# SAMV71_Xplained_Ultra_Audio.net
KiCad netlist of a schematic drawn in Altium Designer
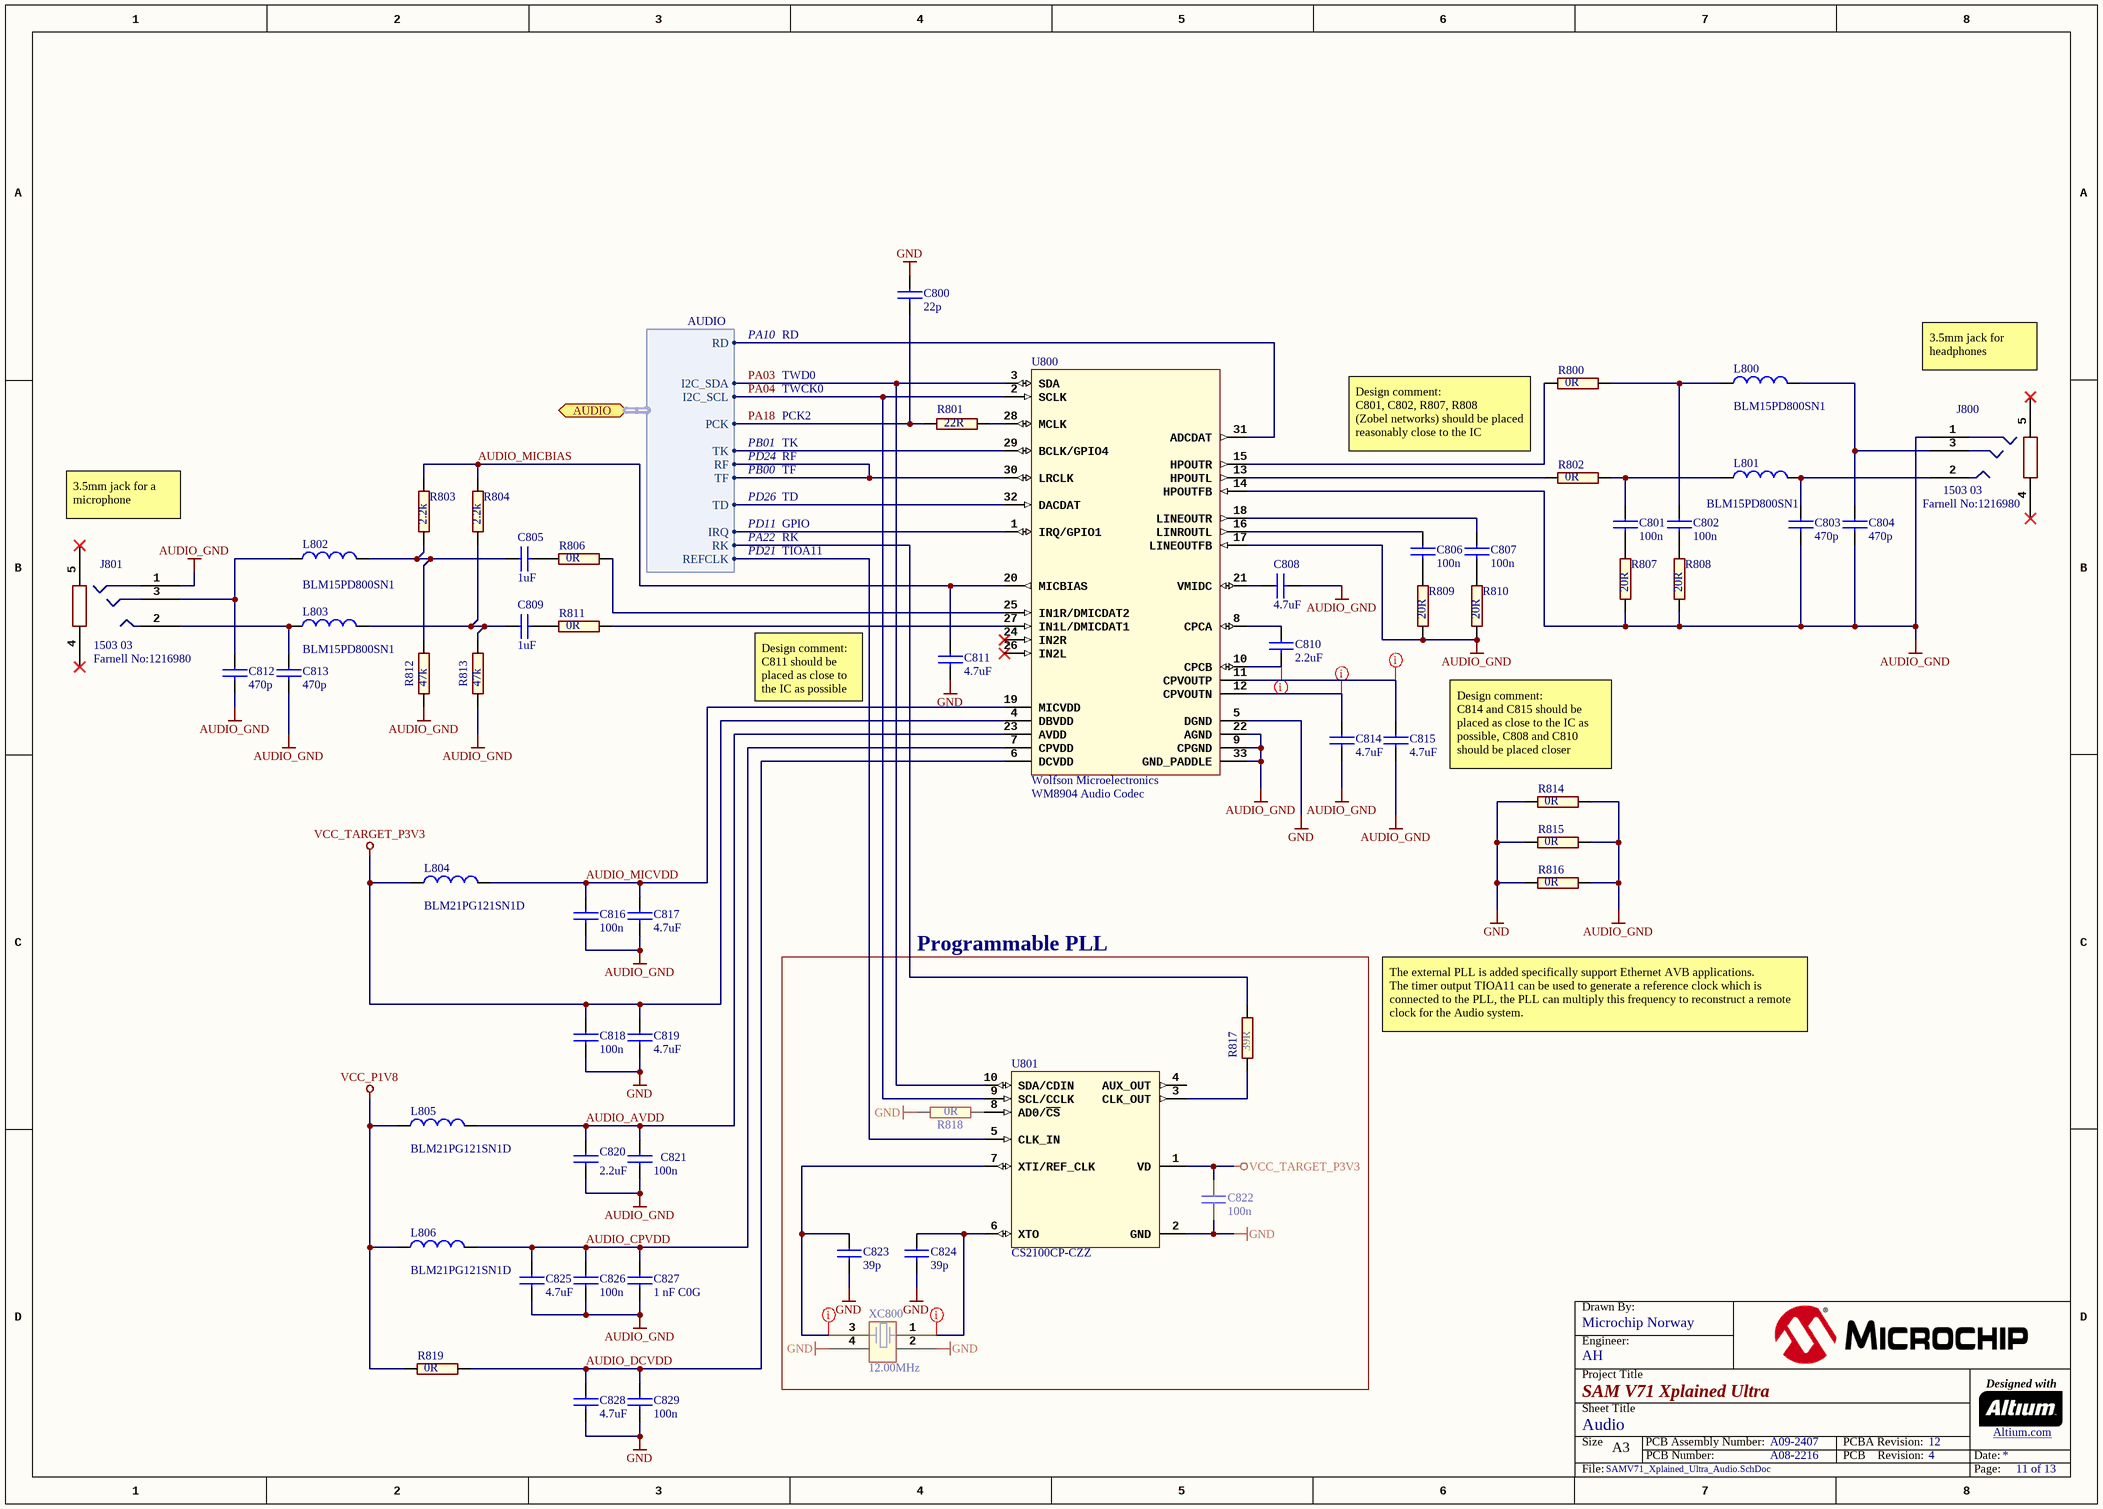
[diagram p0: SAMV71_Xplained_Ultra_Audio.SchDoc]

(export (version "E")
  (design (tool "Eeschema 10.0.6"))
  (components
    (comp (ref "C800")
      (value "22p")
      (footprint "AP1-00001")
      (description "Ceramic capacitor, SMD 0402, NP0, 50V, +/-5%")
      (fields (field (name "TOLERANCE") "50V, +/-5%") (field (name "MANUFACTURER") "YAGEO CORP"))
      (libsource (lib "AltiumDbLib") (part "CAP-NONPOL"))
    )
    (comp (ref "C801")
      (value "100n")
      (footprint "AP1-00001")
      (description "Ceramic capacitor, SMD 0402, X7R, 16V, +/-10%")
      (fields (field (name "TOLERANCE") "16V, +/-10%") (field (name "MANUFACTURER") "Kemet"))
      (libsource (lib "AltiumDbLib") (part "CAP-NONPOL"))
    )
    (comp (ref "C802")
      (value "100n")
      (footprint "AP1-00001")
      (description "Ceramic capacitor, SMD 0402, X7R, 16V, +/-10%")
      (fields (field (name "TOLERANCE") "16V, +/-10%") (field (name "MANUFACTURER") "Kemet"))
      (libsource (lib "AltiumDbLib") (part "CAP-NONPOL"))
    )
    (comp (ref "C803")
      (value "470p")
      (footprint "AP1-00001")
      (description "Ceramic capacitor, SMD 0402, X7R, 50V, +/-10%")
      (fields (field (name "TOLERANCE") "50V, +/-10%") (field (name "MANUFACTURER") "Murata"))
      (libsource (lib "AltiumDbLib") (part "CAP-NONPOL"))
    )
    (comp (ref "C804")
      (value "470p")
      (footprint "AP1-00001")
      (description "Ceramic capacitor, SMD 0402, X7R, 50V, +/-10%")
      (fields (field (name "TOLERANCE") "50V, +/-10%") (field (name "MANUFACTURER") "Murata"))
      (libsource (lib "AltiumDbLib") (part "CAP-NONPOL"))
    )
    (comp (ref "C805")
      (value "1uF")
      (footprint "AP1-00038")
      (description "Ceramic capacitor, SMD 0402, X5R, 10V, ±10 %")
      (fields (field (name "MANUFACTURER") "AVX") (field (name "MPN") "0402ZD105KAT2A"))
      (libsource (lib "AltiumDbLib") (part "CAP-NONPOL"))
    )
    (comp (ref "C806")
      (value "100n")
      (footprint "AP1-00001")
      (description "Ceramic capacitor, SMD 0402, X7R, 16V, +/-10%")
      (fields (field (name "TOLERANCE") "16V, +/-10%") (field (name "MANUFACTURER") "Kemet"))
      (libsource (lib "AltiumDbLib") (part "CAP-NONPOL"))
    )
    (comp (ref "C807")
      (value "100n")
      (footprint "AP1-00001")
      (description "Ceramic capacitor, SMD 0402, X7R, 16V, +/-10%")
      (fields (field (name "TOLERANCE") "16V, +/-10%") (field (name "MANUFACTURER") "Kemet"))
      (libsource (lib "AltiumDbLib") (part "CAP-NONPOL"))
    )
    (comp (ref "C808")
      (value "4.7uF")
      (footprint "AP1-00039")
      (description "Ceramic capacitor, SMD 0603, X5R, 10V, 10% (de31036)")
      (fields (field (name "TOLERANCE") "10%") (field (name "MANUFACTURER") "WALSIN Technology Corporation"))
      (libsource (lib "AltiumDbLib") (part "CAP-NONPOL"))
    )
    (comp (ref "C809")
      (value "1uF")
      (footprint "AP1-00038")
      (description "Ceramic capacitor, SMD 0402, X5R, 10V, ±10 %")
      (fields (field (name "MANUFACTURER") "AVX") (field (name "MPN") "0402ZD105KAT2A"))
      (libsource (lib "AltiumDbLib") (part "CAP-NONPOL"))
    )
    (comp (ref "C810")
      (value "2.2uF")
      (footprint "AP1-00001")
      (description "Ceramic capacitor, SMD 0402, X5R, 6.3V, +/-20%")
      (fields (field (name "TOLERANCE") "Â±20%") (field (name "MANUFACTURER") "Kemet"))
      (libsource (lib "AltiumDbLib") (part "CAP-NONPOL"))
    )
    (comp (ref "C811")
      (value "4.7uF")
      (footprint "AP1-00039")
      (description "Ceramic capacitor, SMD 0603, X5R, 10V, 10% (de31036)")
      (fields (field (name "TOLERANCE") "10%") (field (name "MANUFACTURER") "WALSIN Technology Corporation"))
      (libsource (lib "AltiumDbLib") (part "CAP-NONPOL"))
    )
    (comp (ref "C812")
      (value "470p")
      (footprint "AP1-00001")
      (description "Ceramic capacitor, SMD 0402, X7R, 50V, +/-10%")
      (fields (field (name "TOLERANCE") "50V, +/-10%") (field (name "MANUFACTURER") "Murata"))
      (libsource (lib "AltiumDbLib") (part "CAP-NONPOL"))
    )
    (comp (ref "C813")
      (value "470p")
      (footprint "AP1-00001")
      (description "Ceramic capacitor, SMD 0402, X7R, 50V, +/-10%")
      (fields (field (name "TOLERANCE") "50V, +/-10%") (field (name "MANUFACTURER") "Murata"))
      (libsource (lib "AltiumDbLib") (part "CAP-NONPOL"))
    )
    (comp (ref "C814")
      (value "4.7uF")
      (footprint "AP1-00001")
      (description "Ceramic capacitor, SMD 0402, X5R, 6.3V, +/-20% (de33687)")
      (fields (field (name "TOLERANCE") "+-20%") (field (name "MANUFACTURER") "Murata"))
      (libsource (lib "AltiumDbLib") (part "CAP-NONPOL"))
    )
    (comp (ref "C815")
      (value "4.7uF")
      (footprint "AP1-00001")
      (description "Ceramic capacitor, SMD 0402, X5R, 6.3V, +/-20% (de33687)")
      (fields (field (name "TOLERANCE") "+-20%") (field (name "MANUFACTURER") "Murata"))
      (libsource (lib "AltiumDbLib") (part "CAP-NONPOL"))
    )
    (comp (ref "C816")
      (value "100n")
      (footprint "AP1-00001")
      (description "Ceramic capacitor, SMD 0402, X7R, 16V, +/-10%")
      (fields (field (name "TOLERANCE") "16V, +/-10%") (field (name "MANUFACTURER") "Kemet"))
      (libsource (lib "AltiumDbLib") (part "CAP-NONPOL"))
    )
    (comp (ref "C817")
      (value "4.7uF")
      (footprint "AP1-00039")
      (description "Ceramic capacitor, SMD 0603, X5R, 10V, 10% (de31036)")
      (fields (field (name "TOLERANCE") "10%") (field (name "MANUFACTURER") "WALSIN Technology Corporation"))
      (libsource (lib "AltiumDbLib") (part "CAP-NONPOL"))
    )
    (comp (ref "C818")
      (value "100n")
      (footprint "AP1-00001")
      (description "Ceramic capacitor, SMD 0402, X7R, 16V, +/-10%")
      (fields (field (name "TOLERANCE") "16V, +/-10%") (field (name "MANUFACTURER") "Kemet"))
      (libsource (lib "AltiumDbLib") (part "CAP-NONPOL"))
    )
    (comp (ref "C819")
      (value "4.7uF")
      (footprint "AP1-00039")
      (description "Ceramic capacitor, SMD 0603, X5R, 10V, 10% (de31036)")
      (fields (field (name "TOLERANCE") "10%") (field (name "MANUFACTURER") "WALSIN Technology Corporation"))
      (libsource (lib "AltiumDbLib") (part "CAP-NONPOL"))
    )
    (comp (ref "C820")
      (value "2.2uF")
      (footprint "AP1-00001")
      (description "Ceramic capacitor, SMD 0402, X5R, 6.3V, +/-20%")
      (fields (field (name "TOLERANCE") "Â±20%") (field (name "MANUFACTURER") "Kemet"))
      (libsource (lib "AltiumDbLib") (part "CAP-NONPOL"))
    )
    (comp (ref "C821")
      (value "100n")
      (footprint "AP1-00001")
      (description "Ceramic capacitor, SMD 0402, X7R, 16V, +/-10%")
      (fields (field (name "TOLERANCE") "16V, +/-10%") (field (name "MANUFACTURER") "Kemet"))
      (libsource (lib "AltiumDbLib") (part "CAP-NONPOL"))
    )
    (comp (ref "C822")
      (value "100n")
      (footprint "AP1-00001")
      (description "Ceramic capacitor, SMD 0402, X7R, 16V, +/-10%")
      (fields (field (name "TOLERANCE") "16V, +/-10%") (field (name "MANUFACTURER") "Kemet"))
      (libsource (lib "AltiumDbLib") (part "CAP-NONPOL"))
    )
    (comp (ref "C823")
      (value "39p")
      (footprint "AP1-00001")
      (description "Ceramic capacitor, SMD 0402, NP0, 50V, +/-5%")
      (fields (field (name "TOLERANCE") "50V, +/-5%"))
      (libsource (lib "AltiumDbLib") (part "CAP-NONPOL"))
    )
    (comp (ref "C824")
      (value "39p")
      (footprint "AP1-00001")
      (description "Ceramic capacitor, SMD 0402, NP0, 50V, +/-5%")
      (fields (field (name "TOLERANCE") "50V, +/-5%"))
      (libsource (lib "AltiumDbLib") (part "CAP-NONPOL"))
    )
    (comp (ref "C825")
      (value "4.7uF")
      (footprint "AP1-00039")
      (description "Ceramic capacitor, SMD 0603, X5R, 10V, 10% (de31036)")
      (fields (field (name "TOLERANCE") "10%") (field (name "MANUFACTURER") "WALSIN Technology Corporation"))
      (libsource (lib "AltiumDbLib") (part "CAP-NONPOL"))
    )
    (comp (ref "C826")
      (value "100n")
      (footprint "AP1-00001")
      (description "Ceramic capacitor, SMD 0402, X7R, 16V, +/-10%")
      (fields (field (name "TOLERANCE") "16V, +/-10%") (field (name "MANUFACTURER") "Kemet"))
      (libsource (lib "AltiumDbLib") (part "CAP-NONPOL"))
    )
    (comp (ref "C827")
      (value "1 nF C0G")
      (footprint "AP1-00001")
      (description "Ceramic capacitor, SMD 0402, C0G, 50V, +/-5%")
      (fields (field (name "TOLERANCE") "5%") (field (name "MANUFACTURER") "Murata"))
      (libsource (lib "AltiumDbLib") (part "CAP-NONPOL"))
    )
    (comp (ref "C828")
      (value "4.7uF")
      (footprint "AP1-00039")
      (description "Ceramic capacitor, SMD 0603, X5R, 10V, 10% (de31036)")
      (fields (field (name "TOLERANCE") "10%") (field (name "MANUFACTURER") "WALSIN Technology Corporation"))
      (libsource (lib "AltiumDbLib") (part "CAP-NONPOL"))
    )
    (comp (ref "C829")
      (value "100n")
      (footprint "AP1-00001")
      (description "Ceramic capacitor, SMD 0402, X7R, 16V, +/-10%")
      (fields (field (name "TOLERANCE") "16V, +/-10%") (field (name "MANUFACTURER") "Kemet"))
      (libsource (lib "AltiumDbLib") (part "CAP-NONPOL"))
    )
    (comp (ref "J800")
      (value "Farnell No:1216980")
      (footprint "AP8-00397")
      (description "3.5mm stereo phone jack")
      (fields
        (field (name "ALTIUM_VALUE") "1503 03")
        (field (name "MANUFACTURER") "Lumberg")
        (field (name "MPN") "1503 03")
      )
      (libsource (lib "AltiumDbLib") (part "Jack_Stereo_1503_03"))
    )
    (comp (ref "J801")
      (value "Farnell No:1216980")
      (footprint "AP8-00397")
      (description "3.5mm stereo phone jack")
      (fields
        (field (name "ALTIUM_VALUE") "1503 03")
        (field (name "MANUFACTURER") "Lumberg")
        (field (name "MPN") "1503 03")
      )
      (libsource (lib "") (part "Jack_Stereo_1503_03_1"))
    )
    (comp (ref "L800")
      (value "BLM15PD800SN1")
      (footprint "AP3-00028")
      (description "FERRITE CHIP 80 OHM 1500MA 0402")
      (fields (field (name "TOLERANCE") "±25%") (field (name "MANUFACTURER") "Murata"))
      (libsource (lib "AltiumDbLib") (part "INDUCTOR"))
    )
    (comp (ref "L801")
      (value "BLM15PD800SN1")
      (footprint "AP3-00028")
      (description "FERRITE CHIP 80 OHM 1500MA 0402")
      (fields (field (name "TOLERANCE") "±25%") (field (name "MANUFACTURER") "Murata"))
      (libsource (lib "AltiumDbLib") (part "INDUCTOR"))
    )
    (comp (ref "L802")
      (value "BLM15PD800SN1")
      (footprint "AP3-00028")
      (description "FERRITE CHIP 80 OHM 1500MA 0402")
      (fields (field (name "TOLERANCE") "±25%") (field (name "MANUFACTURER") "Murata"))
      (libsource (lib "AltiumDbLib") (part "INDUCTOR"))
    )
    (comp (ref "L803")
      (value "BLM15PD800SN1")
      (footprint "AP3-00028")
      (description "FERRITE CHIP 80 OHM 1500MA 0402")
      (fields (field (name "TOLERANCE") "±25%") (field (name "MANUFACTURER") "Murata"))
      (libsource (lib "AltiumDbLib") (part "INDUCTOR"))
    )
    (comp (ref "L804")
      (value "BLM21PG121SN1D")
      (footprint "AP3-00104")
      (fields (field (name "MANUFACTURER") "Murata"))
      (libsource (lib "AltiumDbLib") (part "INDUCTOR"))
    )
    (comp (ref "L805")
      (value "BLM21PG121SN1D")
      (footprint "AP3-00104")
      (fields (field (name "MANUFACTURER") "Murata"))
      (libsource (lib "AltiumDbLib") (part "INDUCTOR"))
    )
    (comp (ref "L806")
      (value "BLM21PG121SN1D")
      (footprint "AP3-00104")
      (fields (field (name "MANUFACTURER") "Murata"))
      (libsource (lib "AltiumDbLib") (part "INDUCTOR"))
    )
    (comp (ref "R800")
      (value "0R")
      (footprint "AP2-00000")
      (description "RES 0.0 OHM 1/16W 0402 SMD")
      (fields (field (name "TOLERANCE") "1 %") (field (name "MANUFACTURER") "(n/a)"))
      (libsource (lib "AltiumDbLib") (part "R2"))
    )
    (comp (ref "R801")
      (value "22R")
      (footprint "AP2-00000")
      (description "Thick film resistor, SMD 0402, 1/16W, 1% (de23607)")
      (fields (field (name "TOLERANCE") "1 %") (field (name "MANUFACTURER") "Samsung"))
      (libsource (lib "AltiumDbLib") (part "R2"))
    )
    (comp (ref "R802")
      (value "0R")
      (footprint "AP2-00000")
      (description "RES 0.0 OHM 1/16W 0402 SMD")
      (fields (field (name "TOLERANCE") "1 %") (field (name "MANUFACTURER") "(n/a)"))
      (libsource (lib "AltiumDbLib") (part "R2"))
    )
    (comp (ref "R803")
      (value "2.2k")
      (footprint "AP2-00000")
      (description "Thick film resistor, SMD 0402, 1/16W, 1%")
      (fields (field (name "TOLERANCE") "1 %") (field (name "MANUFACTURER") "ASJ"))
      (libsource (lib "") (part "R2_1"))
    )
    (comp (ref "R804")
      (value "2.2k")
      (footprint "AP2-00000")
      (description "Thick film resistor, SMD 0402, 1/16W, 1%")
      (fields (field (name "TOLERANCE") "1 %") (field (name "MANUFACTURER") "ASJ"))
      (libsource (lib "") (part "R2_1"))
    )
    (comp (ref "R806")
      (value "0R")
      (footprint "AP2-00000")
      (description "RES 0.0 OHM 1/16W 0402 SMD")
      (fields (field (name "TOLERANCE") "1 %") (field (name "MANUFACTURER") "(n/a)"))
      (libsource (lib "AltiumDbLib") (part "R2"))
    )
    (comp (ref "R807")
      (value "20R")
      (footprint "AP2-00000")
      (description "Thick film resistor, SMD 0402, 1/16W, 1%")
      (fields (field (name "TOLERANCE") "1 %") (field (name "MANUFACTURER") "vishay"))
      (libsource (lib "") (part "R2_1"))
    )
    (comp (ref "R808")
      (value "20R")
      (footprint "AP2-00000")
      (description "Thick film resistor, SMD 0402, 1/16W, 1%")
      (fields (field (name "TOLERANCE") "1 %") (field (name "MANUFACTURER") "vishay"))
      (libsource (lib "") (part "R2_1"))
    )
    (comp (ref "R809")
      (value "20R")
      (footprint "AP2-00000")
      (description "Thick film resistor, SMD 0402, 1/16W, 1%")
      (fields (field (name "TOLERANCE") "1 %") (field (name "MANUFACTURER") "vishay"))
      (libsource (lib "") (part "R2_1"))
    )
    (comp (ref "R810")
      (value "20R")
      (footprint "AP2-00000")
      (description "Thick film resistor, SMD 0402, 1/16W, 1%")
      (fields (field (name "TOLERANCE") "1 %") (field (name "MANUFACTURER") "vishay"))
      (libsource (lib "") (part "R2_1"))
    )
    (comp (ref "R811")
      (value "0R")
      (footprint "AP2-00000")
      (description "RES 0.0 OHM 1/16W 0402 SMD")
      (fields (field (name "TOLERANCE") "1 %") (field (name "MANUFACTURER") "(n/a)"))
      (libsource (lib "AltiumDbLib") (part "R2"))
    )
    (comp (ref "R812")
      (value "47k")
      (footprint "AP2-00000")
      (description "Thick film resistor, SMD 0402, 1/16W, 1%")
      (fields (field (name "TOLERANCE") "1 %") (field (name "MANUFACTURER") "KOA"))
      (libsource (lib "") (part "R2_1"))
    )
    (comp (ref "R813")
      (value "47k")
      (footprint "AP2-00000")
      (description "Thick film resistor, SMD 0402, 1/16W, 1%")
      (fields (field (name "TOLERANCE") "1 %") (field (name "MANUFACTURER") "KOA"))
      (libsource (lib "") (part "R2_1"))
    )
    (comp (ref "R814")
      (value "0R")
      (footprint "AP2-00000")
      (description "RES 0.0 OHM 1/16W 0402 SMD")
      (fields (field (name "TOLERANCE") "1 %") (field (name "MANUFACTURER") "(n/a)"))
      (libsource (lib "AltiumDbLib") (part "R2"))
    )
    (comp (ref "R815")
      (value "0R")
      (footprint "AP2-00000")
      (description "RES 0.0 OHM 1/16W 0402 SMD")
      (fields (field (name "TOLERANCE") "1 %") (field (name "MANUFACTURER") "(n/a)"))
      (libsource (lib "AltiumDbLib") (part "R2"))
    )
    (comp (ref "R816")
      (value "0R")
      (footprint "AP2-00000")
      (description "RES 0.0 OHM 1/16W 0402 SMD")
      (fields (field (name "TOLERANCE") "1 %") (field (name "MANUFACTURER") "(n/a)"))
      (libsource (lib "AltiumDbLib") (part "R2"))
    )
    (comp (ref "R817")
      (value "39R")
      (footprint "AP2-00000")
      (description "Thick film resistor, SMD 0402, 1/16W, 1%")
      (fields (field (name "TOLERANCE") "1 %") (field (name "MANUFACTURER") "ASJ"))
      (libsource (lib "") (part "R2_1"))
    )
    (comp (ref "R818")
      (value "0R")
      (footprint "AP2-00000")
      (description "RES 0.0 OHM 1/16W 0402 SMD")
      (fields (field (name "TOLERANCE") "1 %") (field (name "MANUFACTURER") "(n/a)"))
      (libsource (lib "AltiumDbLib") (part "R2"))
    )
    (comp (ref "R819")
      (value "0R")
      (footprint "AP2-00000")
      (description "RES 0.0 OHM 1/16W 0402 SMD")
      (fields (field (name "TOLERANCE") "1 %") (field (name "MANUFACTURER") "(n/a)"))
      (libsource (lib "AltiumDbLib") (part "R2"))
    )
    (comp (ref "U800")
      (value "Wolfson Microelectronics")
      (footprint "AP6-00420")
      (description "Ultra Low Power Codec for Portable Audio Applications")
      (fields
        (field (name "ALTIUM_VALUE") "WM8904 Audio Codec")
        (field (name "MANUFACTURER") "Wolfson microelectronics")
        (field (name "MPN") "WM8904CGEFL/RV")
      )
      (libsource (lib "AltiumDbLib") (part "WM8904"))
    )
    (comp (ref "U801")
      (value "CS2100CP-CZZ")
      (footprint "AP6-00097")
      (description "Programmable Phase-Locked Loop Clock Generator")
      (fields (field (name "MANUFACTURER") "CIRRUS LOGIC") (field (name "MPN") "CS2100CP-CZZR"))
      (libsource (lib "AltiumDbLib") (part "CS2100"))
    )
    (comp (ref "XC800")
      (value "12.00MHz")
      (footprint "AP7-00039")
      (description "Fox FQ5032B 12.0MHz SMD crystal 738B-12")
      (fields (field (name "TOLERANCE") "Â±30ppm") (field (name "MANUFACTURER") "Fox  Electronics"))
      (libsource (lib "AltiumDbLib") (part "CRYSTAL1324"))
    )
  )
  (nets
    (net (code "2") (name "/AUDIO_AVDD") (class "Default")
      (node (ref "C820") (pin "1") (pinfunction "1_1") (pintype "passive"))
      (node (ref "C821") (pin "1") (pinfunction "1_1") (pintype "passive"))
      (node (ref "L805") (pin "2") (pinfunction "2_2") (pintype "passive"))
      (node (ref "U800") (pin "23") (pinfunction "AVDD_23") (pintype "power_in"))
    )
    (net (code "3") (name "/AUDIO_CPVDD") (class "Default")
      (node (ref "C825") (pin "1") (pinfunction "1_1") (pintype "passive"))
      (node (ref "C826") (pin "1") (pinfunction "1_1") (pintype "passive"))
      (node (ref "C827") (pin "1") (pinfunction "1_1") (pintype "passive"))
      (node (ref "L806") (pin "2") (pinfunction "2_2") (pintype "passive"))
      (node (ref "U800") (pin "7") (pinfunction "CPVDD_7") (pintype "power_in"))
    )
    (net (code "4") (name "/AUDIO_DCVDD") (class "Default")
      (node (ref "C828") (pin "1") (pinfunction "1_1") (pintype "passive"))
      (node (ref "C829") (pin "1") (pinfunction "1_1") (pintype "passive"))
      (node (ref "R819") (pin "2") (pinfunction "2_2") (pintype "passive"))
      (node (ref "U800") (pin "6") (pinfunction "DCVDD_6") (pintype "power_in"))
    )
    (net (code "5") (name "/AUDIO_MICBIAS") (class "Default")
      (node (ref "C811") (pin "1") (pinfunction "1_1") (pintype "passive"))
      (node (ref "R803") (pin "2") (pinfunction "2_2") (pintype "passive"))
      (node (ref "R804") (pin "2") (pinfunction "2_2") (pintype "passive"))
      (node (ref "U800") (pin "20") (pinfunction "MICBIAS_20") (pintype "output"))
    )
    (net (code "6") (name "/AUDIO_MICVDD") (class "Default")
      (node (ref "C816") (pin "1") (pinfunction "1_1") (pintype "passive"))
      (node (ref "C817") (pin "1") (pinfunction "1_1") (pintype "passive"))
      (node (ref "L804") (pin "2") (pinfunction "2_2") (pintype "passive"))
      (node (ref "U800") (pin "19") (pinfunction "MICVDD_19") (pintype "power_in"))
    )
    (net (code "7") (name "/IRQ") (class "Default")
      (node (ref "U800") (pin "1") (pinfunction "IRQ/GPIO1_1") (pintype "bidirectional"))
    )
    (net (code "8") (name "/PA03") (class "Default")
      (node (ref "U800") (pin "3") (pinfunction "SDA_3") (pintype "bidirectional"))
      (node (ref "U801") (pin "10") (pinfunction "SDA/CDIN_10") (pintype "bidirectional"))
    )
    (net (code "9") (name "/PA04") (class "Default")
      (node (ref "U800") (pin "2") (pinfunction "SCLK_2") (pintype "input"))
      (node (ref "U801") (pin "9") (pinfunction "SCL/CCLK_9") (pintype "input"))
    )
    (net (code "10") (name "/PA18") (class "Default")
      (node (ref "C800") (pin "2") (pinfunction "2_2") (pintype "passive"))
      (node (ref "R801") (pin "1") (pinfunction "1_1") (pintype "passive"))
    )
    (net (code "11") (name "/RD") (class "Default")
      (node (ref "U800") (pin "31") (pinfunction "ADCDAT_31") (pintype "output"))
    )
    (net (code "12") (name "/REFCLK") (class "Default")
      (node (ref "U801") (pin "5") (pinfunction "CLK_IN_5") (pintype "input"))
    )
    (net (code "13") (name "/RF") (class "Default")
      (node (ref "U800") (pin "30") (pinfunction "LRCLK_30") (pintype "bidirectional"))
    )
    (net (code "14") (name "/RK") (class "Default")
      (node (ref "R817") (pin "2") (pinfunction "2_2") (pintype "passive"))
    )
    (net (code "15") (name "/TD") (class "Default")
      (node (ref "U800") (pin "32") (pinfunction "DACDAT_32") (pintype "input"))
    )
    (net (code "16") (name "/TK") (class "Default")
      (node (ref "U800") (pin "29") (pinfunction "BCLK/GPIO4_29") (pintype "bidirectional"))
    )
    (net (code "18") (name "AUDIO_GND") (class "Default")
      (node (ref "C803") (pin "2") (pinfunction "2_2") (pintype "passive"))
      (node (ref "C804") (pin "2") (pinfunction "2_2") (pintype "passive"))
      (node (ref "C808") (pin "2") (pinfunction "2_2") (pintype "passive"))
      (node (ref "C812") (pin "2") (pinfunction "2_2") (pintype "passive"))
      (node (ref "C813") (pin "2") (pinfunction "2_2") (pintype "passive"))
      (node (ref "C814") (pin "2") (pinfunction "2_2") (pintype "passive"))
      (node (ref "C815") (pin "2") (pinfunction "2_2") (pintype "passive"))
      (node (ref "C816") (pin "2") (pinfunction "2_2") (pintype "passive"))
      (node (ref "C817") (pin "2") (pinfunction "2_2") (pintype "passive"))
      (node (ref "C820") (pin "2") (pinfunction "2_2") (pintype "passive"))
      (node (ref "C821") (pin "2") (pinfunction "2_2") (pintype "passive"))
      (node (ref "C825") (pin "2") (pinfunction "2_2") (pintype "passive"))
      (node (ref "C826") (pin "2") (pinfunction "2_2") (pintype "passive"))
      (node (ref "C827") (pin "2") (pinfunction "2_2") (pintype "passive"))
      (node (ref "J800") (pin "1") (pinfunction "GND_1") (pintype "passive"))
      (node (ref "J801") (pin "1") (pinfunction "GND_1") (pintype "passive"))
      (node (ref "R807") (pin "1") (pinfunction "1_1") (pintype "passive"))
      (node (ref "R808") (pin "1") (pinfunction "1_1") (pintype "passive"))
      (node (ref "R809") (pin "1") (pinfunction "1_1") (pintype "passive"))
      (node (ref "R810") (pin "1") (pinfunction "1_1") (pintype "passive"))
      (node (ref "R812") (pin "1") (pinfunction "1_1") (pintype "passive"))
      (node (ref "R813") (pin "1") (pinfunction "1_1") (pintype "passive"))
      (node (ref "R814") (pin "2") (pinfunction "2_2") (pintype "passive"))
      (node (ref "R815") (pin "2") (pinfunction "2_2") (pintype "passive"))
      (node (ref "R816") (pin "2") (pinfunction "2_2") (pintype "passive"))
      (node (ref "U800") (pin "14") (pinfunction "HPOUTFB_14") (pintype "input"))
      (node (ref "U800") (pin "17") (pinfunction "LINEOUTFB_17") (pintype "input"))
      (node (ref "U800") (pin "22") (pinfunction "AGND_22") (pintype "power_in"))
      (node (ref "U800") (pin "33") (pinfunction "GND_PADDLE_33") (pintype "power_in"))
      (node (ref "U800") (pin "9") (pinfunction "CPGND_9") (pintype "power_in"))
    )
    (net (code "19") (name "GND") (class "Default")
      (node (ref "C800") (pin "1") (pinfunction "1_1") (pintype "passive"))
      (node (ref "C811") (pin "2") (pinfunction "2_2") (pintype "passive"))
      (node (ref "C818") (pin "2") (pinfunction "2_2") (pintype "passive"))
      (node (ref "C819") (pin "2") (pinfunction "2_2") (pintype "passive"))
      (node (ref "C822") (pin "2") (pinfunction "2_2") (pintype "passive"))
      (node (ref "C823") (pin "2") (pinfunction "2_2") (pintype "passive"))
      (node (ref "C824") (pin "2") (pinfunction "2_2") (pintype "passive"))
      (node (ref "C828") (pin "2") (pinfunction "2_2") (pintype "passive"))
      (node (ref "C829") (pin "2") (pinfunction "2_2") (pintype "passive"))
      (node (ref "R814") (pin "1") (pinfunction "1_1") (pintype "passive"))
      (node (ref "R815") (pin "1") (pinfunction "1_1") (pintype "passive"))
      (node (ref "R816") (pin "1") (pinfunction "1_1") (pintype "passive"))
      (node (ref "R818") (pin "1") (pinfunction "1_1") (pintype "passive"))
      (node (ref "U800") (pin "5") (pinfunction "DGND_5") (pintype "power_in"))
      (node (ref "U801") (pin "2") (pinfunction "GND_2") (pintype "power_in"))
      (node (ref "XC800") (pin "2") (pinfunction "2_2") (pintype "passive"))
      (node (ref "XC800") (pin "4") (pinfunction "4_4") (pintype "passive"))
    )
    (net (code "20") (name "Net-(C801-Pad1)") (class "Default")
      (node (ref "C801") (pin "1") (pinfunction "1_1") (pintype "passive"))
      (node (ref "L801") (pin "1") (pinfunction "1_1") (pintype "passive"))
      (node (ref "R802") (pin "2") (pinfunction "2_2") (pintype "passive"))
    )
    (net (code "21") (name "Net-(C801-Pad2)") (class "Default")
      (node (ref "C801") (pin "2") (pinfunction "2_2") (pintype "passive"))
      (node (ref "R807") (pin "2") (pinfunction "2_2") (pintype "passive"))
    )
    (net (code "22") (name "Net-(C802-Pad1)") (class "Default")
      (node (ref "C802") (pin "1") (pinfunction "1_1") (pintype "passive"))
      (node (ref "L800") (pin "1") (pinfunction "1_1") (pintype "passive"))
      (node (ref "R800") (pin "2") (pinfunction "2_2") (pintype "passive"))
    )
    (net (code "23") (name "Net-(C802-Pad2)") (class "Default")
      (node (ref "C802") (pin "2") (pinfunction "2_2") (pintype "passive"))
      (node (ref "R808") (pin "2") (pinfunction "2_2") (pintype "passive"))
    )
    (net (code "24") (name "Net-(C803-Pad1)") (class "Default")
      (node (ref "C803") (pin "1") (pinfunction "1_1") (pintype "passive"))
      (node (ref "J800") (pin "2") (pintype "passive"))
      (node (ref "L801") (pin "2") (pinfunction "2_2") (pintype "passive"))
    )
    (net (code "25") (name "Net-(C804-Pad1)") (class "Default")
      (node (ref "C804") (pin "1") (pinfunction "1_1") (pintype "passive"))
      (node (ref "J800") (pin "3") (pintype "passive"))
      (node (ref "L800") (pin "2") (pinfunction "2_2") (pintype "passive"))
    )
    (net (code "26") (name "Net-(C805-Pad1)") (class "Default")
      (node (ref "C805") (pin "1") (pinfunction "1_1") (pintype "passive"))
      (node (ref "L802") (pin "2") (pinfunction "2_2") (pintype "passive"))
      (node (ref "R803") (pin "1") (pinfunction "1_1") (pintype "passive"))
      (node (ref "R812") (pin "2") (pinfunction "2_2") (pintype "passive"))
    )
    (net (code "27") (name "Net-(C805-Pad2)") (class "Default")
      (node (ref "C805") (pin "2") (pinfunction "2_2") (pintype "passive"))
      (node (ref "R806") (pin "1") (pinfunction "1_1") (pintype "passive"))
    )
    (net (code "28") (name "Net-(C806-Pad2)") (class "Default")
      (node (ref "C806") (pin "2") (pinfunction "2_2") (pintype "passive"))
      (node (ref "R809") (pin "2") (pinfunction "2_2") (pintype "passive"))
    )
    (net (code "29") (name "Net-(C807-Pad2)") (class "Default")
      (node (ref "C807") (pin "2") (pinfunction "2_2") (pintype "passive"))
      (node (ref "R810") (pin "2") (pinfunction "2_2") (pintype "passive"))
    )
    (net (code "30") (name "Net-(C809-Pad1)") (class "Default")
      (node (ref "C809") (pin "1") (pinfunction "1_1") (pintype "passive"))
      (node (ref "L803") (pin "2") (pinfunction "2_2") (pintype "passive"))
      (node (ref "R804") (pin "1") (pinfunction "1_1") (pintype "passive"))
      (node (ref "R813") (pin "2") (pinfunction "2_2") (pintype "passive"))
    )
    (net (code "31") (name "Net-(C809-Pad2)") (class "Default")
      (node (ref "C809") (pin "2") (pinfunction "2_2") (pintype "passive"))
      (node (ref "R811") (pin "1") (pinfunction "1_1") (pintype "passive"))
    )
    (net (code "32") (name "Net-(C812-Pad1)") (class "Default")
      (node (ref "C812") (pin "1") (pinfunction "1_1") (pintype "passive"))
      (node (ref "J801") (pin "3") (pintype "passive"))
      (node (ref "L802") (pin "1") (pinfunction "1_1") (pintype "passive"))
    )
    (net (code "33") (name "Net-(C813-Pad1)") (class "Default")
      (node (ref "C813") (pin "1") (pinfunction "1_1") (pintype "passive"))
      (node (ref "J801") (pin "2") (pintype "passive"))
      (node (ref "L803") (pin "1") (pinfunction "1_1") (pintype "passive"))
    )
    (net (code "34") (name "Net-(U800-CPCA)") (class "Default")
      (node (ref "C810") (pin "1") (pinfunction "1_1") (pintype "passive"))
      (node (ref "U800") (pin "8") (pinfunction "CPCA_8") (pintype "bidirectional"))
    )
    (net (code "35") (name "Net-(U800-CPCB)") (class "Default")
      (node (ref "C810") (pin "2") (pinfunction "2_2") (pintype "passive"))
      (node (ref "U800") (pin "10") (pinfunction "CPCB_10") (pintype "bidirectional"))
    )
    (net (code "36") (name "Net-(U800-CPVOUTN)") (class "Default")
      (node (ref "C814") (pin "1") (pinfunction "1_1") (pintype "passive"))
      (node (ref "U800") (pin "12") (pinfunction "CPVOUTN_12") (pintype "passive"))
    )
    (net (code "37") (name "Net-(U800-CPVOUTP)") (class "Default")
      (node (ref "C815") (pin "1") (pinfunction "1_1") (pintype "passive"))
      (node (ref "U800") (pin "11") (pinfunction "CPVOUTP_11") (pintype "passive"))
    )
    (net (code "38") (name "Net-(U800-HPOUTL)") (class "Default")
      (node (ref "R802") (pin "1") (pinfunction "1_1") (pintype "passive"))
      (node (ref "U800") (pin "13") (pinfunction "HPOUTL_13") (pintype "output"))
    )
    (net (code "39") (name "Net-(U800-HPOUTR)") (class "Default")
      (node (ref "R800") (pin "1") (pinfunction "1_1") (pintype "passive"))
      (node (ref "U800") (pin "15") (pinfunction "HPOUTR_15") (pintype "output"))
    )
    (net (code "40") (name "Net-(U800-IN1L{slash}DMICDAT1)") (class "Default")
      (node (ref "R811") (pin "2") (pinfunction "2_2") (pintype "passive"))
      (node (ref "U800") (pin "27") (pinfunction "IN1L/DMICDAT1_27") (pintype "input"))
    )
    (net (code "41") (name "Net-(U800-IN1R{slash}DMICDAT2)") (class "Default")
      (node (ref "R806") (pin "2") (pinfunction "2_2") (pintype "passive"))
      (node (ref "U800") (pin "25") (pinfunction "IN1R/DMICDAT2_25") (pintype "input"))
    )
    (net (code "42") (name "Net-(U800-LINEOUTR)") (class "Default")
      (node (ref "C807") (pin "1") (pinfunction "1_1") (pintype "passive"))
      (node (ref "U800") (pin "18") (pinfunction "LINEOUTR_18") (pintype "output"))
    )
    (net (code "43") (name "Net-(U800-LINROUTL)") (class "Default")
      (node (ref "C806") (pin "1") (pinfunction "1_1") (pintype "passive"))
      (node (ref "U800") (pin "16") (pinfunction "LINROUTL_16") (pintype "output"))
    )
    (net (code "44") (name "Net-(U800-MCLK)") (class "Default")
      (node (ref "R801") (pin "2") (pinfunction "2_2") (pintype "passive"))
      (node (ref "U800") (pin "28") (pinfunction "MCLK_28") (pintype "bidirectional"))
    )
    (net (code "45") (name "Net-(U800-VMIDC)") (class "Default")
      (node (ref "C808") (pin "1") (pinfunction "1_1") (pintype "passive"))
      (node (ref "U800") (pin "21") (pinfunction "VMIDC_21") (pintype "bidirectional"))
    )
    (net (code "46") (name "Net-(U801-AD0{slash}~{CS})") (class "Default")
      (node (ref "R818") (pin "2") (pinfunction "2_2") (pintype "passive"))
      (node (ref "U801") (pin "8") (pinfunction "AD0/~{CS}_8") (pintype "input"))
    )
    (net (code "47") (name "Net-(U801-CLK_OUT)") (class "Default")
      (node (ref "R817") (pin "1") (pinfunction "1_1") (pintype "passive"))
      (node (ref "U801") (pin "3") (pinfunction "CLK_OUT_3") (pintype "output"))
    )
    (net (code "48") (name "Net-(U801-XTI{slash}REF_CLK)") (class "Default")
      (node (ref "C823") (pin "1") (pinfunction "1_1") (pintype "passive"))
      (node (ref "U801") (pin "7") (pinfunction "XTI/REF_CLK_7") (pintype "bidirectional"))
      (node (ref "XC800") (pin "3") (pinfunction "3_3") (pintype "passive"))
    )
    (net (code "49") (name "Net-(U801-XTO)") (class "Default")
      (node (ref "C824") (pin "1") (pinfunction "1_1") (pintype "passive"))
      (node (ref "U801") (pin "6") (pinfunction "XTO_6") (pintype "bidirectional"))
      (node (ref "XC800") (pin "1") (pinfunction "1_1") (pintype "passive"))
    )
    (net (code "50") (name "VCC_P1V8") (class "Default")
      (node (ref "L805") (pin "1") (pinfunction "1_1") (pintype "passive"))
      (node (ref "L806") (pin "1") (pinfunction "1_1") (pintype "passive"))
      (node (ref "R819") (pin "1") (pinfunction "1_1") (pintype "passive"))
    )
    (net (code "51") (name "VCC_TARGET_P3V3") (class "Default")
      (node (ref "C818") (pin "1") (pinfunction "1_1") (pintype "passive"))
      (node (ref "C819") (pin "1") (pinfunction "1_1") (pintype "passive"))
      (node (ref "C822") (pin "1") (pinfunction "1_1") (pintype "passive"))
      (node (ref "L804") (pin "1") (pinfunction "1_1") (pintype "passive"))
      (node (ref "U800") (pin "4") (pinfunction "DBVDD_4") (pintype "power_in"))
      (node (ref "U801") (pin "1") (pinfunction "VD_1") (pintype "power_in"))
    )
    (net (code "52") (name "unconnected-(J800-Pad4)") (class "Default")
      (node (ref "J800") (pin "4") (pintype "passive+no_connect"))
    )
    (net (code "53") (name "unconnected-(J800-Pad5)") (class "Default")
      (node (ref "J800") (pin "5") (pintype "passive+no_connect"))
    )
    (net (code "54") (name "unconnected-(J801-Pad4)") (class "Default")
      (node (ref "J801") (pin "4") (pintype "passive+no_connect"))
    )
    (net (code "55") (name "unconnected-(J801-Pad5)") (class "Default")
      (node (ref "J801") (pin "5") (pintype "passive+no_connect"))
    )
    (net (code "56") (name "unconnected-(U800-IN2L-Pad26)") (class "Default")
      (node (ref "U800") (pin "26") (pinfunction "IN2L_26") (pintype "input+no_connect"))
    )
    (net (code "57") (name "unconnected-(U800-IN2R-Pad24)") (class "Default")
      (node (ref "U800") (pin "24") (pinfunction "IN2R_24") (pintype "input+no_connect"))
    )
    (net (code "58") (name "unconnected-(U801-AUX_OUT-Pad4)") (class "Default")
      (node (ref "U801") (pin "4") (pinfunction "AUX_OUT_4") (pintype "output"))
    )
  )
)
